# RF_Splitter_active.net
KiCad netlist of a schematic drawn in EAGLE
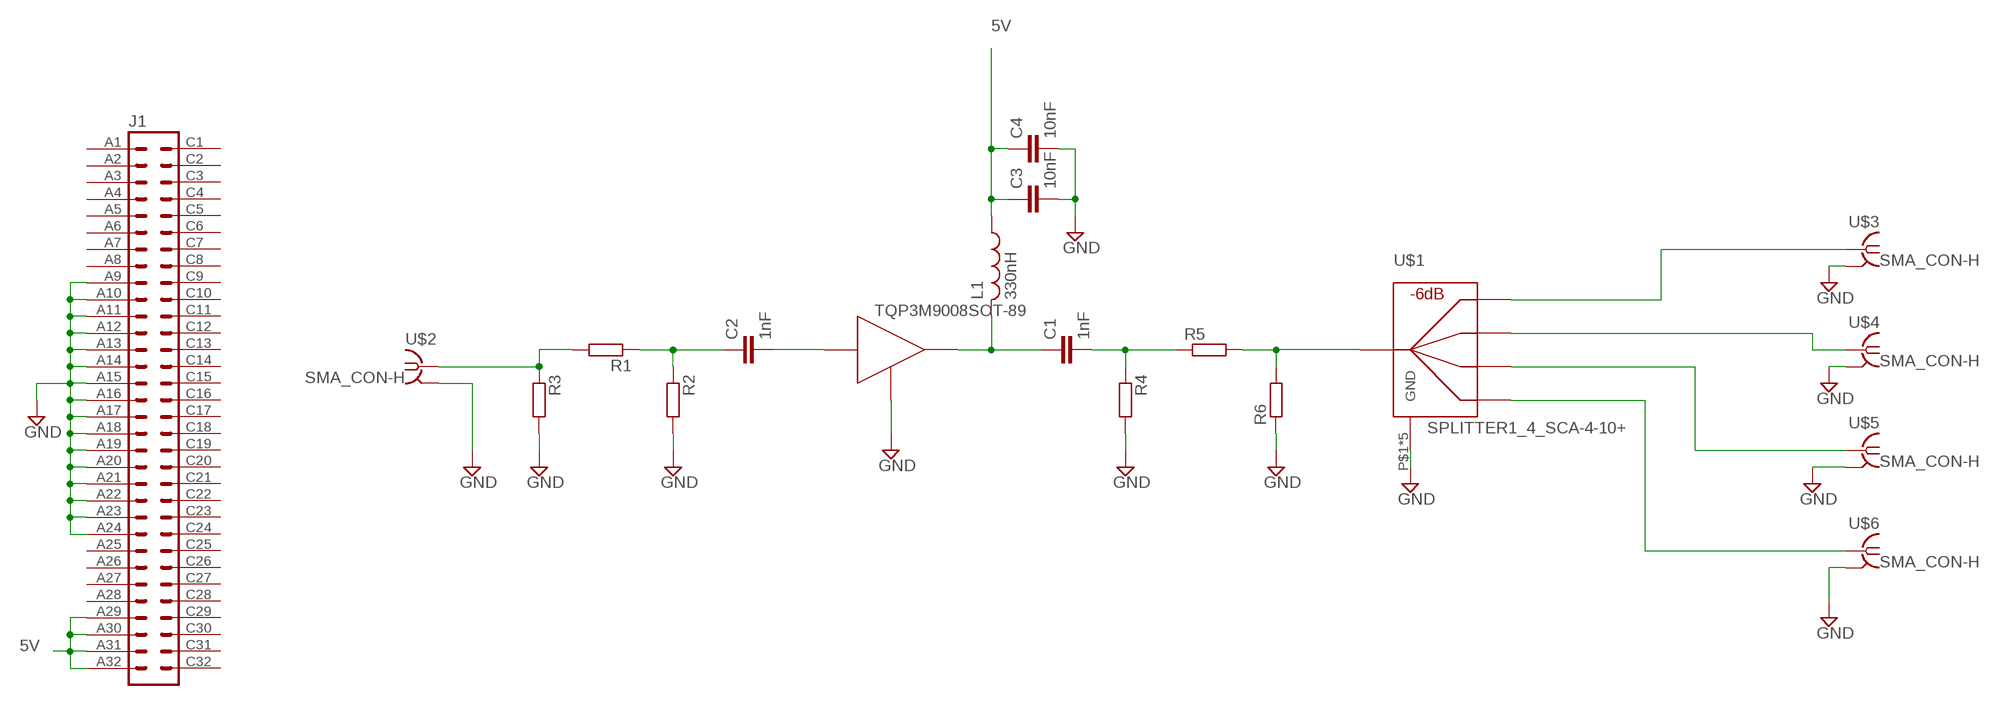
[diagram p0: schematic, sheet 1]

(export (version "E")
  (design (tool "Eeschema 10.0.6"))
  (components
    (comp (ref "C1")
      (value "1nF")
      (footprint "eagle-import:C0603")
      (libsource (lib "eagle-import") (part "C-EUC0603"))
    )
    (comp (ref "C2")
      (value "1nF")
      (footprint "eagle-import:C0603")
      (libsource (lib "eagle-import") (part "C-EUC0603"))
    )
    (comp (ref "C3")
      (value "10nF")
      (footprint "eagle-import:C0603")
      (libsource (lib "eagle-import") (part "C-EUC0603"))
    )
    (comp (ref "C4")
      (value "10nF")
      (footprint "eagle-import:C0603")
      (libsource (lib "eagle-import") (part "C-EUC0603"))
    )
    (comp (ref "J1")
      (value "VG64P")
      (footprint "eagle-import:VG64P")
      (libsource (lib "eagle-import") (part "VG64P"))
    )
    (comp (ref "L1")
      (value "330nH")
      (footprint "eagle-import:L2012C")
      (libsource (lib "eagle-import") (part "L-USL2012C"))
    )
    (comp (ref "R1")
      (value "R-EU_R0603")
      (footprint "eagle-import:R0603")
      (libsource (lib "eagle-import") (part "R-EU_R0603"))
    )
    (comp (ref "R2")
      (value "R-EU_R0603")
      (footprint "eagle-import:R0603")
      (libsource (lib "eagle-import") (part "R-EU_R0603"))
    )
    (comp (ref "R3")
      (value "R-EU_R0603")
      (footprint "eagle-import:R0603")
      (libsource (lib "eagle-import") (part "R-EU_R0603"))
    )
    (comp (ref "R4")
      (value "R-EU_R0603")
      (footprint "eagle-import:R0603")
      (libsource (lib "eagle-import") (part "R-EU_R0603"))
    )
    (comp (ref "R5")
      (value "R-EU_R0603")
      (footprint "eagle-import:R0603")
      (libsource (lib "eagle-import") (part "R-EU_R0603"))
    )
    (comp (ref "R6")
      (value "R-EU_R0603")
      (footprint "eagle-import:R0603")
      (libsource (lib "eagle-import") (part "R-EU_R0603"))
    )
    (comp (ref "U$1")
      (value "SPLITTER1_4_SCA-4-10+")
      (footprint "eagle-import:SCA-4-10+")
      (libsource (lib "eagle-import") (part "SPLITTER1_4_SCA-4-10+"))
    )
    (comp (ref "U$2")
      (value "SMA_CON-H")
      (footprint "eagle-import:BU-SMA-H")
      (libsource (lib "eagle-import") (part "SMA_CON-H"))
    )
    (comp (ref "U$3")
      (value "SMA_CON-H")
      (footprint "eagle-import:BU-SMA-H")
      (libsource (lib "eagle-import") (part "SMA_CON-H"))
    )
    (comp (ref "U$4")
      (value "SMA_CON-H")
      (footprint "eagle-import:BU-SMA-H")
      (libsource (lib "eagle-import") (part "SMA_CON-H"))
    )
    (comp (ref "U$5")
      (value "SMA_CON-H")
      (footprint "eagle-import:BU-SMA-H")
      (libsource (lib "eagle-import") (part "SMA_CON-H"))
    )
    (comp (ref "U$6")
      (value "SMA_CON-H")
      (footprint "eagle-import:BU-SMA-H")
      (libsource (lib "eagle-import") (part "SMA_CON-H"))
    )
    (comp (ref "U$7")
      (value "TQP3M9008SOT-89")
      (footprint "eagle-import:SOT89")
      (libsource (lib "eagle-import") (part "TQP3M9008SOT-89"))
    )
  )
  (nets
    (net (code "1") (name "/5V") (class "Default")
      (node (ref "C3") (pin "1") (pinfunction "1_1") (pintype "passive"))
      (node (ref "C4") (pin "1") (pinfunction "1_1") (pintype "passive"))
      (node (ref "J1") (pin "A29") (pinfunction "A29_A29") (pintype "passive"))
      (node (ref "J1") (pin "A30") (pinfunction "A30_A30") (pintype "passive"))
      (node (ref "J1") (pin "A31") (pinfunction "A31_A31") (pintype "passive"))
      (node (ref "J1") (pin "A32") (pinfunction "A32_A32") (pintype "passive"))
      (node (ref "L1") (pin "1") (pinfunction "1_1") (pintype "passive"))
    )
    (net (code "2") (name "GND") (class "Default")
      (node (ref "C3") (pin "2") (pinfunction "2_2") (pintype "passive"))
      (node (ref "C4") (pin "2") (pinfunction "2_2") (pintype "passive"))
      (node (ref "J1") (pin "A10") (pinfunction "A10_A10") (pintype "passive"))
      (node (ref "J1") (pin "A11") (pinfunction "A11_A11") (pintype "passive"))
      (node (ref "J1") (pin "A12") (pinfunction "A12_A12") (pintype "passive"))
      (node (ref "J1") (pin "A13") (pinfunction "A13_A13") (pintype "passive"))
      (node (ref "J1") (pin "A14") (pinfunction "A14_A14") (pintype "passive"))
      (node (ref "J1") (pin "A15") (pinfunction "A15_A15") (pintype "passive"))
      (node (ref "J1") (pin "A16") (pinfunction "A16_A16") (pintype "passive"))
      (node (ref "J1") (pin "A17") (pinfunction "A17_A17") (pintype "passive"))
      (node (ref "J1") (pin "A18") (pinfunction "A18_A18") (pintype "passive"))
      (node (ref "J1") (pin "A19") (pinfunction "A19_A19") (pintype "passive"))
      (node (ref "J1") (pin "A20") (pinfunction "A20_A20") (pintype "passive"))
      (node (ref "J1") (pin "A21") (pinfunction "A21_A21") (pintype "passive"))
      (node (ref "J1") (pin "A22") (pinfunction "A22_A22") (pintype "passive"))
      (node (ref "J1") (pin "A23") (pinfunction "A23_A23") (pintype "passive"))
      (node (ref "J1") (pin "A24") (pinfunction "A24_A24") (pintype "passive"))
      (node (ref "J1") (pin "A9") (pinfunction "A9_A9") (pintype "passive"))
      (node (ref "R2") (pin "2") (pinfunction "2_2") (pintype "passive"))
      (node (ref "R3") (pin "2") (pinfunction "2_2") (pintype "passive"))
      (node (ref "R4") (pin "2") (pinfunction "2_2") (pintype "passive"))
      (node (ref "R6") (pin "1") (pinfunction "1_1") (pintype "passive"))
      (node (ref "U$1") (pin "P$1") (pinfunction "GND_P$1") (pintype "bidirectional"))
      (node (ref "U$1") (pin "P$2") (pinfunction "GND_P$2") (pintype "bidirectional"))
      (node (ref "U$1") (pin "P$4") (pinfunction "GND_P$4") (pintype "bidirectional"))
      (node (ref "U$1") (pin "P$5") (pinfunction "GND_P$5") (pintype "bidirectional"))
      (node (ref "U$1") (pin "P$8") (pinfunction "GND_P$8") (pintype "bidirectional"))
      (node (ref "U$2") (pin "2") (pinfunction "GND_2") (pintype "passive"))
      (node (ref "U$2") (pin "3") (pinfunction "GND_3") (pintype "passive"))
      (node (ref "U$2") (pin "4") (pinfunction "GND_4") (pintype "passive"))
      (node (ref "U$2") (pin "5") (pinfunction "GND_5") (pintype "passive"))
      (node (ref "U$3") (pin "2") (pinfunction "GND_2") (pintype "passive"))
      (node (ref "U$3") (pin "3") (pinfunction "GND_3") (pintype "passive"))
      (node (ref "U$3") (pin "4") (pinfunction "GND_4") (pintype "passive"))
      (node (ref "U$3") (pin "5") (pinfunction "GND_5") (pintype "passive"))
      (node (ref "U$4") (pin "2") (pinfunction "GND_2") (pintype "passive"))
      (node (ref "U$4") (pin "3") (pinfunction "GND_3") (pintype "passive"))
      (node (ref "U$4") (pin "4") (pinfunction "GND_4") (pintype "passive"))
      (node (ref "U$4") (pin "5") (pinfunction "GND_5") (pintype "passive"))
      (node (ref "U$5") (pin "2") (pinfunction "GND_2") (pintype "passive"))
      (node (ref "U$5") (pin "3") (pinfunction "GND_3") (pintype "passive"))
      (node (ref "U$5") (pin "4") (pinfunction "GND_4") (pintype "passive"))
      (node (ref "U$5") (pin "5") (pinfunction "GND_5") (pintype "passive"))
      (node (ref "U$6") (pin "2") (pinfunction "GND_2") (pintype "passive"))
      (node (ref "U$6") (pin "3") (pinfunction "GND_3") (pintype "passive"))
      (node (ref "U$6") (pin "4") (pinfunction "GND_4") (pintype "passive"))
      (node (ref "U$6") (pin "5") (pinfunction "GND_5") (pintype "passive"))
      (node (ref "U$7") (pin "2") (pinfunction "GND_2") (pintype "bidirectional"))
      (node (ref "U$7") (pin "2@1") (pinfunction "GND_2@1") (pintype "bidirectional"))
    )
    (net (code "3") (name "Net-(C1-Pad2)") (class "Default")
      (node (ref "C1") (pin "2") (pinfunction "2_2") (pintype "passive"))
      (node (ref "R4") (pin "1") (pinfunction "1_1") (pintype "passive"))
      (node (ref "R5") (pin "1") (pinfunction "1_1") (pintype "passive"))
    )
    (net (code "4") (name "Net-(C2-Pad1)") (class "Default")
      (node (ref "C2") (pin "1") (pinfunction "1_1") (pintype "passive"))
      (node (ref "R1") (pin "1") (pinfunction "1_1") (pintype "passive"))
      (node (ref "R2") (pin "1") (pinfunction "1_1") (pintype "passive"))
    )
    (net (code "5") (name "Net-(R1-Pad2)") (class "Default")
      (node (ref "R1") (pin "2") (pinfunction "2_2") (pintype "passive"))
      (node (ref "R3") (pin "1") (pinfunction "1_1") (pintype "passive"))
      (node (ref "U$2") (pin "1") (pinfunction "1_1") (pintype "passive"))
    )
    (net (code "6") (name "Net-(U$1-P$1)") (class "Default")
      (node (ref "R5") (pin "2") (pinfunction "2_2") (pintype "passive"))
      (node (ref "R6") (pin "2") (pinfunction "2_2") (pintype "passive"))
      (node (ref "U$1") (pin "P$3") (pinfunction "P$1_P$3") (pintype "bidirectional"))
    )
    (net (code "7") (name "Net-(U$1-P$2)") (class "Default")
      (node (ref "U$1") (pin "P$6") (pinfunction "P$2_P$6") (pintype "bidirectional"))
      (node (ref "U$3") (pin "1") (pinfunction "1_1") (pintype "passive"))
    )
    (net (code "8") (name "Net-(U$1-P$3)") (class "Default")
      (node (ref "U$1") (pin "P$7") (pinfunction "P$3_P$7") (pintype "bidirectional"))
      (node (ref "U$4") (pin "1") (pinfunction "1_1") (pintype "passive"))
    )
    (net (code "9") (name "Net-(U$1-P$4)") (class "Default")
      (node (ref "U$1") (pin "P$9") (pinfunction "P$4_P$9") (pintype "bidirectional"))
      (node (ref "U$5") (pin "1") (pinfunction "1_1") (pintype "passive"))
    )
    (net (code "10") (name "Net-(U$1-P$5)") (class "Default")
      (node (ref "U$1") (pin "P$10") (pinfunction "P$5_P$10") (pintype "bidirectional"))
      (node (ref "U$6") (pin "1") (pinfunction "1_1") (pintype "passive"))
    )
    (net (code "11") (name "Net-(U$7-IN)") (class "Default")
      (node (ref "C2") (pin "2") (pinfunction "2_2") (pintype "passive"))
      (node (ref "U$7") (pin "1") (pinfunction "IN_1") (pintype "bidirectional"))
    )
    (net (code "12") (name "Net-(U$7-OUT)") (class "Default")
      (node (ref "C1") (pin "1") (pinfunction "1_1") (pintype "passive"))
      (node (ref "L1") (pin "2") (pinfunction "2_2") (pintype "passive"))
      (node (ref "U$7") (pin "3") (pinfunction "OUT_3") (pintype "bidirectional"))
    )
    (net (code "13") (name "unconnected-(J1-PadA1)") (class "Default")
      (node (ref "J1") (pin "A1") (pinfunction "A1_A1") (pintype "passive"))
    )
    (net (code "14") (name "unconnected-(J1-PadA2)") (class "Default")
      (node (ref "J1") (pin "A2") (pinfunction "A2_A2") (pintype "passive"))
    )
    (net (code "15") (name "unconnected-(J1-PadA3)") (class "Default")
      (node (ref "J1") (pin "A3") (pinfunction "A3_A3") (pintype "passive"))
    )
    (net (code "16") (name "unconnected-(J1-PadA4)") (class "Default")
      (node (ref "J1") (pin "A4") (pinfunction "A4_A4") (pintype "passive"))
    )
    (net (code "17") (name "unconnected-(J1-PadA5)") (class "Default")
      (node (ref "J1") (pin "A5") (pinfunction "A5_A5") (pintype "passive"))
    )
    (net (code "18") (name "unconnected-(J1-PadA6)") (class "Default")
      (node (ref "J1") (pin "A6") (pinfunction "A6_A6") (pintype "passive"))
    )
    (net (code "19") (name "unconnected-(J1-PadA7)") (class "Default")
      (node (ref "J1") (pin "A7") (pinfunction "A7_A7") (pintype "passive"))
    )
    (net (code "20") (name "unconnected-(J1-PadA8)") (class "Default")
      (node (ref "J1") (pin "A8") (pinfunction "A8_A8") (pintype "passive"))
    )
    (net (code "21") (name "unconnected-(J1-PadA25)") (class "Default")
      (node (ref "J1") (pin "A25") (pinfunction "A25_A25") (pintype "passive"))
    )
    (net (code "22") (name "unconnected-(J1-PadA26)") (class "Default")
      (node (ref "J1") (pin "A26") (pinfunction "A26_A26") (pintype "passive"))
    )
    (net (code "23") (name "unconnected-(J1-PadA27)") (class "Default")
      (node (ref "J1") (pin "A27") (pinfunction "A27_A27") (pintype "passive"))
    )
    (net (code "24") (name "unconnected-(J1-PadA28)") (class "Default")
      (node (ref "J1") (pin "A28") (pinfunction "A28_A28") (pintype "passive"))
    )
    (net (code "25") (name "unconnected-(J1-PadC1)") (class "Default")
      (node (ref "J1") (pin "C1") (pinfunction "C1_C1") (pintype "passive"))
    )
    (net (code "26") (name "unconnected-(J1-PadC2)") (class "Default")
      (node (ref "J1") (pin "C2") (pinfunction "C2_C2") (pintype "passive"))
    )
    (net (code "27") (name "unconnected-(J1-PadC3)") (class "Default")
      (node (ref "J1") (pin "C3") (pinfunction "C3_C3") (pintype "passive"))
    )
    (net (code "28") (name "unconnected-(J1-PadC4)") (class "Default")
      (node (ref "J1") (pin "C4") (pinfunction "C4_C4") (pintype "passive"))
    )
    (net (code "29") (name "unconnected-(J1-PadC5)") (class "Default")
      (node (ref "J1") (pin "C5") (pinfunction "C5_C5") (pintype "passive"))
    )
    (net (code "30") (name "unconnected-(J1-PadC6)") (class "Default")
      (node (ref "J1") (pin "C6") (pinfunction "C6_C6") (pintype "passive"))
    )
    (net (code "31") (name "unconnected-(J1-PadC7)") (class "Default")
      (node (ref "J1") (pin "C7") (pinfunction "C7_C7") (pintype "passive"))
    )
    (net (code "32") (name "unconnected-(J1-PadC8)") (class "Default")
      (node (ref "J1") (pin "C8") (pinfunction "C8_C8") (pintype "passive"))
    )
    (net (code "33") (name "unconnected-(J1-PadC9)") (class "Default")
      (node (ref "J1") (pin "C9") (pinfunction "C9_C9") (pintype "passive"))
    )
    (net (code "34") (name "unconnected-(J1-PadC10)") (class "Default")
      (node (ref "J1") (pin "C10") (pinfunction "C10_C10") (pintype "passive"))
    )
    (net (code "35") (name "unconnected-(J1-PadC11)") (class "Default")
      (node (ref "J1") (pin "C11") (pinfunction "C11_C11") (pintype "passive"))
    )
    (net (code "36") (name "unconnected-(J1-PadC12)") (class "Default")
      (node (ref "J1") (pin "C12") (pinfunction "C12_C12") (pintype "passive"))
    )
    (net (code "37") (name "unconnected-(J1-PadC13)") (class "Default")
      (node (ref "J1") (pin "C13") (pinfunction "C13_C13") (pintype "passive"))
    )
    (net (code "38") (name "unconnected-(J1-PadC14)") (class "Default")
      (node (ref "J1") (pin "C14") (pinfunction "C14_C14") (pintype "passive"))
    )
    (net (code "39") (name "unconnected-(J1-PadC15)") (class "Default")
      (node (ref "J1") (pin "C15") (pinfunction "C15_C15") (pintype "passive"))
    )
    (net (code "40") (name "unconnected-(J1-PadC16)") (class "Default")
      (node (ref "J1") (pin "C16") (pinfunction "C16_C16") (pintype "passive"))
    )
    (net (code "41") (name "unconnected-(J1-PadC17)") (class "Default")
      (node (ref "J1") (pin "C17") (pinfunction "C17_C17") (pintype "passive"))
    )
    (net (code "42") (name "unconnected-(J1-PadC18)") (class "Default")
      (node (ref "J1") (pin "C18") (pinfunction "C18_C18") (pintype "passive"))
    )
    (net (code "43") (name "unconnected-(J1-PadC19)") (class "Default")
      (node (ref "J1") (pin "C19") (pinfunction "C19_C19") (pintype "passive"))
    )
    (net (code "44") (name "unconnected-(J1-PadC20)") (class "Default")
      (node (ref "J1") (pin "C20") (pinfunction "C20_C20") (pintype "passive"))
    )
    (net (code "45") (name "unconnected-(J1-PadC21)") (class "Default")
      (node (ref "J1") (pin "C21") (pinfunction "C21_C21") (pintype "passive"))
    )
    (net (code "46") (name "unconnected-(J1-PadC22)") (class "Default")
      (node (ref "J1") (pin "C22") (pinfunction "C22_C22") (pintype "passive"))
    )
    (net (code "47") (name "unconnected-(J1-PadC23)") (class "Default")
      (node (ref "J1") (pin "C23") (pinfunction "C23_C23") (pintype "passive"))
    )
    (net (code "48") (name "unconnected-(J1-PadC24)") (class "Default")
      (node (ref "J1") (pin "C24") (pinfunction "C24_C24") (pintype "passive"))
    )
    (net (code "49") (name "unconnected-(J1-PadC25)") (class "Default")
      (node (ref "J1") (pin "C25") (pinfunction "C25_C25") (pintype "passive"))
    )
    (net (code "50") (name "unconnected-(J1-PadC26)") (class "Default")
      (node (ref "J1") (pin "C26") (pinfunction "C26_C26") (pintype "passive"))
    )
    (net (code "51") (name "unconnected-(J1-PadC27)") (class "Default")
      (node (ref "J1") (pin "C27") (pinfunction "C27_C27") (pintype "passive"))
    )
    (net (code "52") (name "unconnected-(J1-PadC28)") (class "Default")
      (node (ref "J1") (pin "C28") (pinfunction "C28_C28") (pintype "passive"))
    )
    (net (code "53") (name "unconnected-(J1-PadC29)") (class "Default")
      (node (ref "J1") (pin "C29") (pinfunction "C29_C29") (pintype "passive"))
    )
    (net (code "54") (name "unconnected-(J1-PadC30)") (class "Default")
      (node (ref "J1") (pin "C30") (pinfunction "C30_C30") (pintype "passive"))
    )
    (net (code "55") (name "unconnected-(J1-PadC31)") (class "Default")
      (node (ref "J1") (pin "C31") (pinfunction "C31_C31") (pintype "passive"))
    )
    (net (code "56") (name "unconnected-(J1-PadC32)") (class "Default")
      (node (ref "J1") (pin "C32") (pinfunction "C32_C32") (pintype "passive"))
    )
  )
)
